# design.net
KiCad netlist of a schematic drawn in Altium Designer
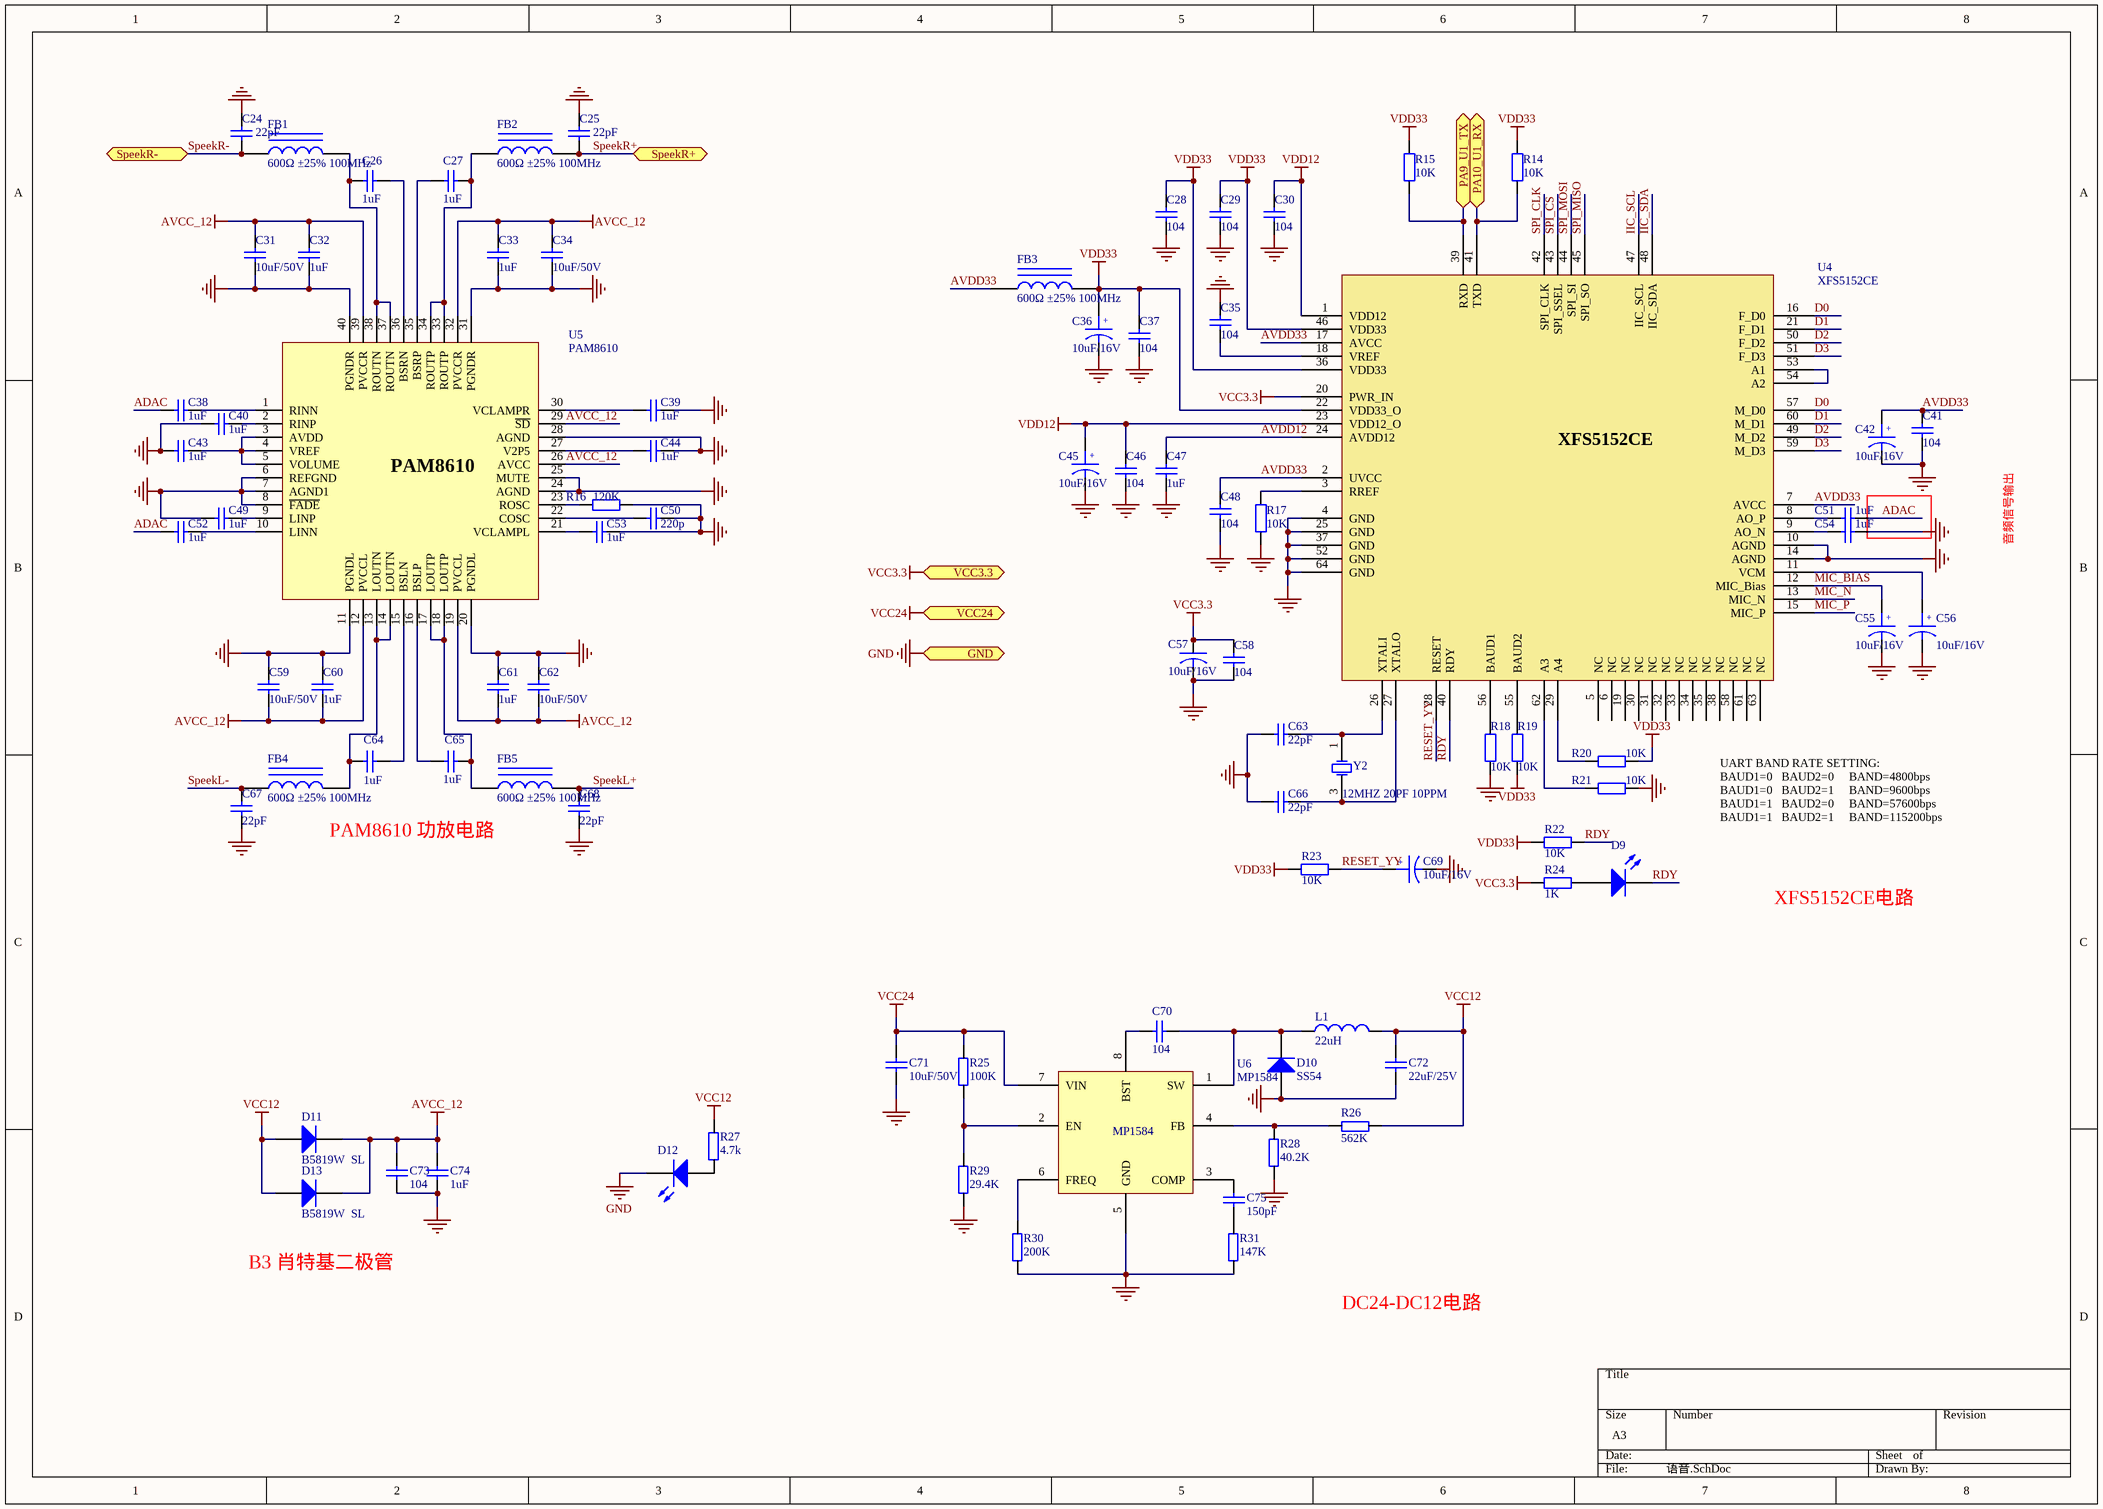
[diagram p0: 语音.SchDoc]

(export (version "E")
  (design (tool "Eeschema 10.0.6"))
  (components
    (comp (ref "C24")
      (value "22pF")
      (footprint "0603_C")
      (description "Capacitor (Semiconductor SIM Model)")
      (fields (field (name "PUBLISHER") "Altium Limited"))
      (libsource (lib "Miscellaneous Devices") (part "Cap Semi"))
    )
    (comp (ref "C25")
      (value "22pF")
      (footprint "0603_C")
      (description "Capacitor (Semiconductor SIM Model)")
      (fields (field (name "PUBLISHER") "Altium Limited"))
      (libsource (lib "Miscellaneous Devices") (part "Cap Semi"))
    )
    (comp (ref "C26")
      (value "1uF")
      (footprint "0603_C")
      (description "Capacitor (Semiconductor SIM Model)")
      (fields (field (name "PUBLISHER") "Altium Limited"))
      (libsource (lib "Miscellaneous Devices") (part "Cap Semi"))
    )
    (comp (ref "C27")
      (value "1uF")
      (footprint "0603_C")
      (description "Capacitor (Semiconductor SIM Model)")
      (fields (field (name "PUBLISHER") "Altium Limited"))
      (libsource (lib "Miscellaneous Devices") (part "Cap Semi"))
    )
    (comp (ref "C28")
      (value "104")
      (footprint "0603_C")
      (description "Capacitor (Semiconductor SIM Model)")
      (fields (field (name "PUBLISHER") "Altium Limited"))
      (libsource (lib "Miscellaneous Devices") (part "Cap Semi"))
    )
    (comp (ref "C29")
      (value "104")
      (footprint "0603_C")
      (description "Capacitor (Semiconductor SIM Model)")
      (fields (field (name "PUBLISHER") "Altium Limited"))
      (libsource (lib "Miscellaneous Devices") (part "Cap Semi"))
    )
    (comp (ref "C30")
      (value "104")
      (footprint "0603_C")
      (description "Capacitor (Semiconductor SIM Model)")
      (fields (field (name "PUBLISHER") "Altium Limited"))
      (libsource (lib "Miscellaneous Devices") (part "Cap Semi"))
    )
    (comp (ref "C31")
      (value "10uF/50V")
      (footprint "1206_C")
      (description "电容")
      (fields (field (name "PUBLISHER") "Altium Limited"))
      (libsource (lib "*") (part "Cap NP"))
    )
    (comp (ref "C32")
      (value "1uF")
      (footprint "0603_C")
      (description "Capacitor (Semiconductor SIM Model)")
      (fields (field (name "PUBLISHER") "Altium Limited"))
      (libsource (lib "Miscellaneous Devices") (part "Cap Semi"))
    )
    (comp (ref "C33")
      (value "1uF")
      (footprint "0603_C")
      (description "Capacitor (Semiconductor SIM Model)")
      (fields (field (name "PUBLISHER") "Altium Limited"))
      (libsource (lib "Miscellaneous Devices") (part "Cap Semi"))
    )
    (comp (ref "C34")
      (value "10uF/50V")
      (footprint "1206_C")
      (description "电容")
      (fields (field (name "PUBLISHER") "Altium Limited"))
      (libsource (lib "*") (part "Cap NP"))
    )
    (comp (ref "C35")
      (value "104")
      (footprint "0603_C")
      (description "Capacitor (Semiconductor SIM Model)")
      (fields (field (name "PUBLISHER") "Altium Limited"))
      (libsource (lib "Miscellaneous Devices") (part "Cap Semi"))
    )
    (comp (ref "C36") (value "10uF/16V") (footprint "3216") (libsource (lib "*") (part "CAP POL")))
    (comp (ref "C37")
      (value "104")
      (footprint "0603_C")
      (description "Capacitor (Semiconductor SIM Model)")
      (fields (field (name "PUBLISHER") "Altium Limited"))
      (libsource (lib "Miscellaneous Devices") (part "Cap Semi"))
    )
    (comp (ref "C38")
      (value "1uF")
      (footprint "0603_C")
      (description "Capacitor (Semiconductor SIM Model)")
      (fields (field (name "PUBLISHER") "Altium Limited"))
      (libsource (lib "Miscellaneous Devices") (part "Cap Semi"))
    )
    (comp (ref "C39")
      (value "1uF")
      (footprint "0603_C")
      (description "Capacitor (Semiconductor SIM Model)")
      (fields (field (name "PUBLISHER") "Altium Limited"))
      (libsource (lib "Miscellaneous Devices") (part "Cap Semi"))
    )
    (comp (ref "C40")
      (value "1uF")
      (footprint "0603_C")
      (description "Capacitor (Semiconductor SIM Model)")
      (fields (field (name "PUBLISHER") "Altium Limited"))
      (libsource (lib "Miscellaneous Devices") (part "Cap Semi"))
    )
    (comp (ref "C41")
      (value "104")
      (footprint "0603_C")
      (description "Capacitor (Semiconductor SIM Model)")
      (fields (field (name "PUBLISHER") "Altium Limited"))
      (libsource (lib "Miscellaneous Devices") (part "Cap Semi"))
    )
    (comp (ref "C42") (value "10uF/16V") (footprint "3216") (libsource (lib "*") (part "CAP POL")))
    (comp (ref "C43")
      (value "1uF")
      (footprint "0603_C")
      (description "Capacitor (Semiconductor SIM Model)")
      (fields (field (name "PUBLISHER") "Altium Limited"))
      (libsource (lib "Miscellaneous Devices") (part "Cap Semi"))
    )
    (comp (ref "C44")
      (value "1uF")
      (footprint "0603_C")
      (description "Capacitor (Semiconductor SIM Model)")
      (fields (field (name "PUBLISHER") "Altium Limited"))
      (libsource (lib "Miscellaneous Devices") (part "Cap Semi"))
    )
    (comp (ref "C45") (value "10uF/16V") (footprint "3216") (libsource (lib "*") (part "CAP POL")))
    (comp (ref "C46")
      (value "104")
      (footprint "0603_C")
      (description "Capacitor (Semiconductor SIM Model)")
      (fields (field (name "PUBLISHER") "Altium Limited"))
      (libsource (lib "Miscellaneous Devices") (part "Cap Semi"))
    )
    (comp (ref "C47")
      (value "1uF")
      (footprint "0603_C")
      (description "Capacitor (Semiconductor SIM Model)")
      (fields (field (name "PUBLISHER") "Altium Limited"))
      (libsource (lib "Miscellaneous Devices") (part "Cap Semi"))
    )
    (comp (ref "C48")
      (value "104")
      (footprint "0603_C")
      (description "Capacitor (Semiconductor SIM Model)")
      (fields (field (name "PUBLISHER") "Altium Limited"))
      (libsource (lib "Miscellaneous Devices") (part "Cap Semi"))
    )
    (comp (ref "C49")
      (value "1uF")
      (footprint "0603_C")
      (description "Capacitor (Semiconductor SIM Model)")
      (fields (field (name "PUBLISHER") "Altium Limited"))
      (libsource (lib "Miscellaneous Devices") (part "Cap Semi"))
    )
    (comp (ref "C50")
      (value "220p")
      (footprint "0603_C")
      (description "Capacitor (Semiconductor SIM Model)")
      (fields (field (name "PUBLISHER") "Altium Limited"))
      (libsource (lib "Miscellaneous Devices") (part "Cap Semi"))
    )
    (comp (ref "C51")
      (value "1uF")
      (footprint "0603_C")
      (description "Capacitor (Semiconductor SIM Model)")
      (fields (field (name "PUBLISHER") "Altium Limited"))
      (libsource (lib "Miscellaneous Devices") (part "Cap Semi"))
    )
    (comp (ref "C52")
      (value "1uF")
      (footprint "0603_C")
      (description "Capacitor (Semiconductor SIM Model)")
      (fields (field (name "PUBLISHER") "Altium Limited"))
      (libsource (lib "Miscellaneous Devices") (part "Cap Semi"))
    )
    (comp (ref "C53")
      (value "1uF")
      (footprint "0603_C")
      (description "Capacitor (Semiconductor SIM Model)")
      (fields (field (name "PUBLISHER") "Altium Limited"))
      (libsource (lib "Miscellaneous Devices") (part "Cap Semi"))
    )
    (comp (ref "C54")
      (value "1uF")
      (footprint "0603_C")
      (description "Capacitor (Semiconductor SIM Model)")
      (fields (field (name "PUBLISHER") "Altium Limited"))
      (libsource (lib "Miscellaneous Devices") (part "Cap Semi"))
    )
    (comp (ref "C55") (value "10uF/16V") (footprint "3216") (libsource (lib "*") (part "CAP POL")))
    (comp (ref "C56") (value "10uF/16V") (footprint "3216") (libsource (lib "*") (part "CAP POL")))
    (comp (ref "C57")
      (value "10uF/16V")
      (footprint "3216")
      (description "Capacitor")
      (libsource (lib "*") (part "CAPACITOR"))
    )
    (comp (ref "C58")
      (value "104")
      (footprint "0603_C")
      (description "Capacitor (Semiconductor SIM Model)")
      (fields (field (name "PUBLISHER") "Altium Limited"))
      (libsource (lib "Miscellaneous Devices") (part "Cap Semi"))
    )
    (comp (ref "C59")
      (value "10uF/50V")
      (footprint "1206_C")
      (description "电容")
      (fields (field (name "PUBLISHER") "Altium Limited"))
      (libsource (lib "*") (part "Cap NP"))
    )
    (comp (ref "C60")
      (value "1uF")
      (footprint "0603_C")
      (description "Capacitor (Semiconductor SIM Model)")
      (fields (field (name "PUBLISHER") "Altium Limited"))
      (libsource (lib "Miscellaneous Devices") (part "Cap Semi"))
    )
    (comp (ref "C61")
      (value "1uF")
      (footprint "0603_C")
      (description "Capacitor (Semiconductor SIM Model)")
      (fields (field (name "PUBLISHER") "Altium Limited"))
      (libsource (lib "Miscellaneous Devices") (part "Cap Semi"))
    )
    (comp (ref "C62")
      (value "10uF/50V")
      (footprint "1206_C")
      (description "电容")
      (fields (field (name "PUBLISHER") "Altium Limited"))
      (libsource (lib "*") (part "Cap NP"))
    )
    (comp (ref "C63")
      (value "22pF")
      (footprint "0603_C")
      (description "电容")
      (fields (field (name "PUBLISHER") "Altium Limited"))
      (libsource (lib "*") (part "Cap NP"))
    )
    (comp (ref "C64")
      (value "1uF")
      (footprint "0603_C")
      (description "Capacitor (Semiconductor SIM Model)")
      (fields (field (name "PUBLISHER") "Altium Limited"))
      (libsource (lib "Miscellaneous Devices") (part "Cap Semi"))
    )
    (comp (ref "C65")
      (value "1uF")
      (footprint "0603_C")
      (description "Capacitor (Semiconductor SIM Model)")
      (fields (field (name "PUBLISHER") "Altium Limited"))
      (libsource (lib "Miscellaneous Devices") (part "Cap Semi"))
    )
    (comp (ref "C66")
      (value "22pF")
      (footprint "0603_C")
      (description "电容")
      (fields (field (name "PUBLISHER") "Altium Limited"))
      (libsource (lib "*") (part "Cap NP"))
    )
    (comp (ref "C67")
      (value "22pF")
      (footprint "0603_C")
      (description "Capacitor (Semiconductor SIM Model)")
      (fields (field (name "PUBLISHER") "Altium Limited"))
      (libsource (lib "Miscellaneous Devices") (part "Cap Semi"))
    )
    (comp (ref "C68")
      (value "22pF")
      (footprint "0603_C")
      (description "Capacitor (Semiconductor SIM Model)")
      (fields (field (name "PUBLISHER") "Altium Limited"))
      (libsource (lib "Miscellaneous Devices") (part "Cap Semi"))
    )
    (comp (ref "C69") (value "10uF/16V") (footprint "3216") (libsource (lib "*") (part "CAP POL")))
    (comp (ref "C70")
      (value "104")
      (footprint "0603_C")
      (description "Capacitor (Semiconductor SIM Model)")
      (fields (field (name "PUBLISHER") "Altium Limited"))
      (libsource (lib "Miscellaneous Devices") (part "Cap Semi"))
    )
    (comp (ref "C71")
      (value "10uF/50V")
      (footprint "1206_C")
      (description "Capacitor (Semiconductor SIM Model)")
      (fields (field (name "PUBLISHER") "Altium Limited"))
      (libsource (lib "Miscellaneous Devices") (part "Cap Semi"))
    )
    (comp (ref "C72")
      (value "22uF/25V")
      (footprint "0805_C")
      (description "Capacitor (Semiconductor SIM Model)")
      (fields (field (name "PUBLISHER") "Altium Limited"))
      (libsource (lib "Miscellaneous Devices") (part "Cap Semi"))
    )
    (comp (ref "C73")
      (value "104")
      (footprint "0603_C")
      (description "Capacitor (Semiconductor SIM Model)")
      (fields (field (name "PUBLISHER") "Altium Limited"))
      (libsource (lib "Miscellaneous Devices") (part "Cap Semi"))
    )
    (comp (ref "C74")
      (value "1uF")
      (footprint "0603_C")
      (description "Capacitor (Semiconductor SIM Model)")
      (fields (field (name "PUBLISHER") "Altium Limited"))
      (libsource (lib "Miscellaneous Devices") (part "Cap Semi"))
    )
    (comp (ref "C75")
      (value "150pF")
      (footprint "0603_C")
      (description "Capacitor (Semiconductor SIM Model)")
      (fields (field (name "PUBLISHER") "Altium Limited"))
      (libsource (lib "Miscellaneous Devices") (part "Cap Semi"))
    )
    (comp (ref "D9")
      (value "红灯 0805")
      (footprint "LC-0805_LED_S1")
      (description "Typical INFRARED GaAs LED")
      (fields (field (name "PUBLISHER") "Altium Limited"))
      (libsource (lib "继电器板_1") (part "LED0"))
    )
    (comp (ref "D10")
      (value "SS54")
      (footprint "SMA(DO-214AC)_S1")
      (description "二极管")
      (libsource (lib "Miscellaneous Devices LC") (part "SMA(DO-214AC) SS54"))
    )
    (comp (ref "D11")
      (value "B5819W  SL")
      (footprint "SOD-123")
      (description "肖特基二极管")
      (libsource (lib "Miscellaneous Devices LC") (part "SOD-123 B5819W  SL"))
    )
    (comp (ref "D12")
      (value "蓝灯 0805")
      (footprint "LC-0805_LED_S1")
      (description "Typical INFRARED GaAs LED")
      (fields (field (name "PUBLISHER") "Altium Limited"))
      (libsource (lib "继电器板_1") (part "LED0"))
    )
    (comp (ref "D13")
      (value "B5819W  SL")
      (footprint "SOD-123")
      (description "肖特基二极管")
      (libsource (lib "Miscellaneous Devices LC") (part "SOD-123 B5819W  SL"))
    )
    (comp (ref "FB1")
      (value "600Ω ±25% 100MHz")
      (footprint "0805_L")
      (description "贴片磁珠")
      (libsource (lib "Miscellaneous Devices LC") (part "0805 600Ω 25% 100MHz"))
    )
    (comp (ref "FB2")
      (value "600Ω ±25% 100MHz")
      (footprint "0805_L")
      (description "贴片磁珠")
      (libsource (lib "Miscellaneous Devices LC") (part "0805 600Ω 25% 100MHz"))
    )
    (comp (ref "FB3")
      (value "600Ω ±25% 100MHz")
      (footprint "0805_L")
      (description "贴片磁珠")
      (libsource (lib "Miscellaneous Devices LC") (part "0805 600Ω 25% 100MHz"))
    )
    (comp (ref "FB4")
      (value "600Ω ±25% 100MHz")
      (footprint "0805_L")
      (description "贴片磁珠")
      (libsource (lib "Miscellaneous Devices LC") (part "0805 600Ω 25% 100MHz"))
    )
    (comp (ref "FB5")
      (value "600Ω ±25% 100MHz")
      (footprint "0805_L")
      (description "贴片磁珠")
      (libsource (lib "Miscellaneous Devices LC") (part "0805 600Ω 25% 100MHz"))
    )
    (comp (ref "L1")
      (value "22uH")
      (footprint "L-7*7*4mm-S")
      (description "Inductor")
      (fields (field (name "PUBLISHER") "Altium Limited"))
      (libsource (lib "Miscellaneous Devices") (part "Inductor"))
    )
    (comp (ref "R14")
      (value "10K")
      (footprint "0603_R")
      (description "Resistor")
      (fields (field (name "PUBLISHER") "Altium Limited"))
      (libsource (lib "") (part "Res2_3"))
    )
    (comp (ref "R15")
      (value "10K")
      (footprint "0603_R")
      (description "Resistor")
      (fields (field (name "PUBLISHER") "Altium Limited"))
      (libsource (lib "") (part "Res2_2"))
    )
    (comp (ref "R16")
      (value "120K")
      (footprint "0603_R")
      (description "Resistor")
      (fields (field (name "PUBLISHER") "Altium Limited"))
      (libsource (lib "") (part "Res2_1"))
    )
    (comp (ref "R17")
      (value "10K")
      (footprint "0603_R")
      (description "Resistor")
      (fields (field (name "PUBLISHER") "Altium Limited"))
      (libsource (lib "") (part "Res2_3"))
    )
    (comp (ref "R18")
      (value "10K")
      (footprint "0603_R")
      (description "Resistor")
      (fields (field (name "PUBLISHER") "Altium Limited"))
      (libsource (lib "") (part "Res2_2"))
    )
    (comp (ref "R19")
      (value "10K")
      (footprint "0603_R")
      (description "Resistor")
      (fields (field (name "PUBLISHER") "Altium Limited"))
      (libsource (lib "") (part "Res2_2"))
    )
    (comp (ref "R20")
      (value "10K")
      (footprint "0603_R")
      (description "Resistor")
      (fields (field (name "PUBLISHER") "Altium Limited"))
      (libsource (lib "*") (part "Res2"))
    )
    (comp (ref "R21")
      (value "10K")
      (footprint "0603_R")
      (description "Resistor")
      (fields (field (name "PUBLISHER") "Altium Limited"))
      (libsource (lib "") (part "Res2_1"))
    )
    (comp (ref "R22")
      (value "10K")
      (footprint "0603_R")
      (description "Resistor")
      (fields (field (name "PUBLISHER") "Altium Limited"))
      (libsource (lib "*") (part "Res2"))
    )
    (comp (ref "R23")
      (value "10K")
      (footprint "0603_R")
      (description "Resistor")
      (fields (field (name "PUBLISHER") "Altium Limited"))
      (libsource (lib "*") (part "Res2"))
    )
    (comp (ref "R24")
      (value "1K")
      (footprint "0603_R")
      (description "Resistor")
      (fields (field (name "PUBLISHER") "Altium Limited"))
      (libsource (lib "*") (part "Res2"))
    )
    (comp (ref "R25")
      (value "100K")
      (footprint "0603_R")
      (libsource (lib "Explorer STM32F407封装库") (part "R_2"))
    )
    (comp (ref "R26")
      (value "562K")
      (footprint "0603_R")
      (libsource (lib "Explorer STM32F407封装库") (part "R_2"))
    )
    (comp (ref "R27")
      (value "4.7k")
      (footprint "0603_R")
      (libsource (lib "Explorer STM32F407封装库") (part "R_2"))
    )
    (comp (ref "R28")
      (value "40.2K")
      (footprint "0603_R")
      (libsource (lib "Explorer STM32F407封装库") (part "R_2"))
    )
    (comp (ref "R29")
      (value "29.4K")
      (footprint "0603_R")
      (libsource (lib "Explorer STM32F407封装库") (part "R_2"))
    )
    (comp (ref "R30")
      (value "200K")
      (footprint "0603_R")
      (libsource (lib "Explorer STM32F407封装库") (part "R_2"))
    )
    (comp (ref "R31")
      (value "147K")
      (footprint "0603_R")
      (libsource (lib "Explorer STM32F407封装库") (part "R_2"))
    )
    (comp (ref "U4")
      (value "XFS5152CE")
      (footprint "LQFP-64_10x10x05P")
      (libsource (lib "*") (part "XFS5152-2"))
    )
    (comp (ref "U5")
      (value "PAM8610")
      (footprint "QFN50P600X600X80-40N")
      (libsource (lib "my third") (part "PAM8610功放芯片"))
    )
    (comp (ref "U6")
      (value "MP1584")
      (footprint "LC-SOIC-8_EP_150MIL")
      (libsource (lib "磁导航") (part "MP1584EN"))
    )
    (comp (ref "Y2")
      (value "12MHZ 20PF 10PPM")
      (footprint "SMD-3225_4P")
      (description "贴片晶振")
      (libsource (lib "Miscellaneous Devices LC") (part "SMD-3225_4P  12MHZ 20PF 10PPM"))
    )
  )
  (nets
    (net (code "1") (name "/ADAC") (class "Default")
      (node (ref "C38") (pin "1") (pinfunction "1_1") (pintype "passive"))
      (node (ref "C51") (pin "1") (pinfunction "1_1") (pintype "passive"))
      (node (ref "C52") (pin "1") (pinfunction "1_1") (pintype "passive"))
    )
    (net (code "2") (name "/AVDD12") (class "Default")
      (node (ref "C47") (pin "2") (pinfunction "2_2") (pintype "passive"))
      (node (ref "U4") (pin "24") (pinfunction "AVDD12_24") (pintype "passive"))
    )
    (net (code "3") (name "/AVDD33") (class "Default")
      (node (ref "C41") (pin "1") (pinfunction "1_1") (pintype "passive"))
      (node (ref "C42") (pin "1") (pinfunction "1_1") (pintype "passive"))
      (node (ref "C48") (pin "1") (pinfunction "1_1") (pintype "passive"))
      (node (ref "FB3") (pin "1") (pinfunction "1_1") (pintype "passive"))
      (node (ref "U4") (pin "17") (pinfunction "AVCC_17") (pintype "passive"))
      (node (ref "U4") (pin "2") (pinfunction "UVCC_2") (pintype "passive"))
      (node (ref "U4") (pin "7") (pinfunction "AVCC_7") (pintype "passive"))
    )
    (net (code "4") (name "/D0") (class "Default")
      (node (ref "U4") (pin "16") (pinfunction "F_D0_16") (pintype "passive"))
      (node (ref "U4") (pin "57") (pinfunction "M_D0_57") (pintype "passive"))
    )
    (net (code "5") (name "/D1") (class "Default")
      (node (ref "U4") (pin "21") (pinfunction "F_D1_21") (pintype "passive"))
      (node (ref "U4") (pin "60") (pinfunction "M_D1_60") (pintype "passive"))
    )
    (net (code "6") (name "/D2") (class "Default")
      (node (ref "U4") (pin "49") (pinfunction "M_D2_49") (pintype "passive"))
      (node (ref "U4") (pin "50") (pinfunction "F_D2_50") (pintype "passive"))
    )
    (net (code "7") (name "/D3") (class "Default")
      (node (ref "U4") (pin "51") (pinfunction "F_D3_51") (pintype "passive"))
      (node (ref "U4") (pin "59") (pinfunction "M_D3_59") (pintype "passive"))
    )
    (net (code "8") (name "/IIC_SCL") (class "Default")
      (node (ref "U4") (pin "47") (pinfunction "IIC_SCL_47") (pintype "passive"))
    )
    (net (code "9") (name "/IIC_SDA") (class "Default")
      (node (ref "U4") (pin "48") (pinfunction "IIC_SDA_48") (pintype "passive"))
    )
    (net (code "10") (name "/MIC_BIAS") (class "Default")
      (node (ref "C55") (pin "1") (pinfunction "1_1") (pintype "passive"))
      (node (ref "U4") (pin "12") (pinfunction "MIC_Bias_12") (pintype "passive"))
    )
    (net (code "11") (name "/MIC_N") (class "Default")
      (node (ref "U4") (pin "13") (pinfunction "MIC_N_13") (pintype "passive"))
    )
    (net (code "12") (name "/MIC_P") (class "Default")
      (node (ref "U4") (pin "15") (pinfunction "MIC_P_15") (pintype "passive"))
    )
    (net (code "13") (name "/PA9_U1_TX") (class "Default")
      (node (ref "R15") (pin "2") (pinfunction "2_2") (pintype "passive"))
      (node (ref "U4") (pin "39") (pinfunction "RXD_39") (pintype "passive"))
    )
    (net (code "14") (name "/PA10_U1_RX") (class "Default")
      (node (ref "R14") (pin "1") (pinfunction "1_1") (pintype "passive"))
      (node (ref "U4") (pin "41") (pinfunction "TXD_41") (pintype "passive"))
    )
    (net (code "15") (name "/RDY") (class "Default")
      (node (ref "D9") (pin "K") (pinfunction "K_K") (pintype "passive"))
      (node (ref "R22") (pin "2") (pinfunction "2_2") (pintype "passive"))
      (node (ref "U4") (pin "40") (pinfunction "RDY_40") (pintype "passive"))
    )
    (net (code "16") (name "/RESET_YY") (class "Default")
      (node (ref "C69") (pin "1") (pinfunction "1_1") (pintype "passive"))
      (node (ref "R23") (pin "2") (pinfunction "2_2") (pintype "passive"))
      (node (ref "U4") (pin "28") (pinfunction "RESET_28") (pintype "passive"))
    )
    (net (code "17") (name "/SPI_CLK") (class "Default")
      (node (ref "U4") (pin "42") (pinfunction "SPI_CLK_42") (pintype "passive"))
    )
    (net (code "18") (name "/SPI_CS") (class "Default")
      (node (ref "U4") (pin "43") (pinfunction "SPI_SSEL_43") (pintype "passive"))
    )
    (net (code "19") (name "/SPI_MISO") (class "Default")
      (node (ref "U4") (pin "45") (pinfunction "SPI_SO_45") (pintype "passive"))
    )
    (net (code "20") (name "/SPI_MOSI") (class "Default")
      (node (ref "U4") (pin "44") (pinfunction "SPI_SI_44") (pintype "passive"))
    )
    (net (code "21") (name "/SpeekL+") (class "Default")
      (node (ref "C68") (pin "2") (pinfunction "2_2") (pintype "passive"))
      (node (ref "FB5") (pin "2") (pinfunction "2_2") (pintype "passive"))
    )
    (net (code "22") (name "/SpeekL-") (class "Default")
      (node (ref "C67") (pin "2") (pinfunction "2_2") (pintype "passive"))
      (node (ref "FB4") (pin "1") (pinfunction "1_1") (pintype "passive"))
    )
    (net (code "23") (name "/SpeekR+") (class "Default")
      (node (ref "C25") (pin "2") (pinfunction "2_2") (pintype "passive"))
      (node (ref "FB2") (pin "2") (pinfunction "2_2") (pintype "passive"))
    )
    (net (code "24") (name "/SpeekR-") (class "Default")
      (node (ref "C24") (pin "2") (pinfunction "2_2") (pintype "passive"))
      (node (ref "FB1") (pin "1") (pinfunction "1_1") (pintype "passive"))
    )
    (net (code "25") (name "AVCC_12") (class "Default")
      (node (ref "C31") (pin "1") (pinfunction "1_1") (pintype "passive"))
      (node (ref "C32") (pin "1") (pinfunction "1_1") (pintype "passive"))
      (node (ref "C33") (pin "1") (pinfunction "1_1") (pintype "passive"))
      (node (ref "C34") (pin "1") (pinfunction "1_1") (pintype "passive"))
      (node (ref "C59") (pin "1") (pinfunction "1_1") (pintype "passive"))
      (node (ref "C60") (pin "1") (pinfunction "1_1") (pintype "passive"))
      (node (ref "C61") (pin "1") (pinfunction "1_1") (pintype "passive"))
      (node (ref "C62") (pin "1") (pinfunction "1_1") (pintype "passive"))
      (node (ref "C73") (pin "1") (pinfunction "1_1") (pintype "passive"))
      (node (ref "C74") (pin "1") (pinfunction "1_1") (pintype "passive"))
      (node (ref "D11") (pin "2") (pinfunction "K_2") (pintype "passive"))
      (node (ref "D13") (pin "2") (pinfunction "K_2") (pintype "passive"))
      (node (ref "U5") (pin "12") (pinfunction "PVCCL_12") (pintype "passive"))
      (node (ref "U5") (pin "19") (pinfunction "PVCCL_19") (pintype "passive"))
      (node (ref "U5") (pin "26") (pinfunction "AVCC_26") (pintype "passive"))
      (node (ref "U5") (pin "29") (pinfunction "~{SD}_29") (pintype "passive"))
      (node (ref "U5") (pin "32") (pinfunction "PVCCR_32") (pintype "passive"))
      (node (ref "U5") (pin "39") (pinfunction "PVCCR_39") (pintype "passive"))
    )
    (net (code "26") (name "GND") (class "Default")
      (node (ref "C24") (pin "1") (pinfunction "1_1") (pintype "passive"))
      (node (ref "C25") (pin "1") (pinfunction "1_1") (pintype "passive"))
      (node (ref "C28") (pin "2") (pinfunction "2_2") (pintype "passive"))
      (node (ref "C29") (pin "2") (pinfunction "2_2") (pintype "passive"))
      (node (ref "C30") (pin "2") (pinfunction "2_2") (pintype "passive"))
      (node (ref "C31") (pin "2") (pinfunction "2_2") (pintype "passive"))
      (node (ref "C32") (pin "2") (pinfunction "2_2") (pintype "passive"))
      (node (ref "C33") (pin "2") (pinfunction "2_2") (pintype "passive"))
      (node (ref "C34") (pin "2") (pinfunction "2_2") (pintype "passive"))
      (node (ref "C35") (pin "1") (pinfunction "1_1") (pintype "passive"))
      (node (ref "C36") (pin "2") (pinfunction "2_2") (pintype "passive"))
      (node (ref "C37") (pin "2") (pinfunction "2_2") (pintype "passive"))
      (node (ref "C39") (pin "2") (pinfunction "2_2") (pintype "passive"))
      (node (ref "C40") (pin "1") (pinfunction "1_1") (pintype "passive"))
      (node (ref "C41") (pin "2") (pinfunction "2_2") (pintype "passive"))
      (node (ref "C42") (pin "2") (pinfunction "2_2") (pintype "passive"))
      (node (ref "C43") (pin "1") (pinfunction "1_1") (pintype "passive"))
      (node (ref "C44") (pin "2") (pinfunction "2_2") (pintype "passive"))
      (node (ref "C45") (pin "2") (pinfunction "2_2") (pintype "passive"))
      (node (ref "C46") (pin "2") (pinfunction "2_2") (pintype "passive"))
      (node (ref "C47") (pin "1") (pinfunction "1_1") (pintype "passive"))
      (node (ref "C48") (pin "2") (pinfunction "2_2") (pintype "passive"))
      (node (ref "C49") (pin "1") (pinfunction "1_1") (pintype "passive"))
      (node (ref "C50") (pin "2") (pinfunction "2_2") (pintype "passive"))
      (node (ref "C53") (pin "2") (pinfunction "2_2") (pintype "passive"))
      (node (ref "C54") (pin "1") (pinfunction "1_1") (pintype "passive"))
      (node (ref "C55") (pin "2") (pinfunction "2_2") (pintype "passive"))
      (node (ref "C56") (pin "2") (pinfunction "2_2") (pintype "passive"))
      (node (ref "C57") (pin "2") (pinfunction "2_2") (pintype "passive"))
      (node (ref "C58") (pin "2") (pinfunction "2_2") (pintype "passive"))
      (node (ref "C59") (pin "2") (pinfunction "2_2") (pintype "passive"))
      (node (ref "C60") (pin "2") (pinfunction "2_2") (pintype "passive"))
      (node (ref "C61") (pin "2") (pinfunction "2_2") (pintype "passive"))
      (node (ref "C62") (pin "2") (pinfunction "2_2") (pintype "passive"))
      (node (ref "C63") (pin "1") (pinfunction "1_1") (pintype "passive"))
      (node (ref "C66") (pin "1") (pinfunction "1_1") (pintype "passive"))
      (node (ref "C67") (pin "1") (pinfunction "1_1") (pintype "passive"))
      (node (ref "C68") (pin "1") (pinfunction "1_1") (pintype "passive"))
      (node (ref "C69") (pin "2") (pinfunction "2_2") (pintype "passive"))
      (node (ref "C71") (pin "2") (pinfunction "2_2") (pintype "passive"))
      (node (ref "C72") (pin "1") (pinfunction "1_1") (pintype "passive"))
      (node (ref "C73") (pin "2") (pinfunction "2_2") (pintype "passive"))
      (node (ref "C74") (pin "2") (pinfunction "2_2") (pintype "passive"))
      (node (ref "D10") (pin "1") (pinfunction "A_1") (pintype "passive"))
      (node (ref "D12") (pin "K") (pinfunction "K_K") (pintype "passive"))
      (node (ref "R16") (pin "1") (pinfunction "1_1") (pintype "passive"))
      (node (ref "R17") (pin "1") (pinfunction "1_1") (pintype "passive"))
      (node (ref "R18") (pin "2") (pinfunction "2_2") (pintype "passive"))
      (node (ref "R21") (pin "1") (pinfunction "1_1") (pintype "passive"))
      (node (ref "R28") (pin "2") (pintype "passive"))
      (node (ref "R29") (pin "2") (pintype "passive"))
      (node (ref "R30") (pin "2") (pintype "passive"))
      (node (ref "R31") (pin "2") (pintype "passive"))
      (node (ref "U4") (pin "10") (pinfunction "AGND_10") (pintype "passive"))
      (node (ref "U4") (pin "14") (pinfunction "AGND_14") (pintype "passive"))
      (node (ref "U4") (pin "25") (pinfunction "GND_25") (pintype "passive"))
      (node (ref "U4") (pin "37") (pinfunction "GND_37") (pintype "passive"))
      (node (ref "U4") (pin "4") (pinfunction "GND_4") (pintype "passive"))
      (node (ref "U4") (pin "52") (pinfunction "GND_52") (pintype "passive"))
      (node (ref "U4") (pin "64") (pinfunction "GND_64") (pintype "passive"))
      (node (ref "U5") (pin "11") (pinfunction "PGNDL_11") (pintype "passive"))
      (node (ref "U5") (pin "20") (pinfunction "PGNDL_20") (pintype "passive"))
      (node (ref "U5") (pin "24") (pinfunction "AGND_24") (pintype "passive"))
      (node (ref "U5") (pin "25") (pinfunction "MUTE_25") (pintype "passive"))
      (node (ref "U5") (pin "28") (pinfunction "AGND_28") (pintype "passive"))
      (node (ref "U5") (pin "31") (pinfunction "PGNDR_31") (pintype "passive"))
      (node (ref "U5") (pin "40") (pinfunction "PGNDR_40") (pintype "passive"))
      (node (ref "U5") (pin "6") (pinfunction "REFGND_6") (pintype "passive"))
      (node (ref "U5") (pin "7") (pinfunction "AGND1_7") (pintype "passive"))
      (node (ref "U5") (pin "8") (pinfunction "~{FADE}_8") (pintype "passive"))
      (node (ref "U6") (pin "5") (pinfunction "GND_5") (pintype "passive"))
    )
    (net (code "27") (name "Net-(C26-Pad1)") (class "Default")
      (node (ref "C26") (pin "1") (pinfunction "1_1") (pintype "passive"))
      (node (ref "FB1") (pin "2") (pinfunction "2_2") (pintype "passive"))
      (node (ref "U5") (pin "37") (pinfunction "ROUTN_37") (pintype "passive"))
      (node (ref "U5") (pin "38") (pinfunction "ROUTN_38") (pintype "passive"))
    )
    (net (code "28") (name "Net-(C27-Pad2)") (class "Default")
      (node (ref "C27") (pin "2") (pinfunction "2_2") (pintype "passive"))
      (node (ref "FB2") (pin "1") (pinfunction "1_1") (pintype "passive"))
      (node (ref "U5") (pin "33") (pinfunction "ROUTP_33") (pintype "passive"))
      (node (ref "U5") (pin "34") (pinfunction "ROUTP_34") (pintype "passive"))
    )
    (net (code "29") (name "Net-(C64-Pad2)") (class "Default")
      (node (ref "C64") (pin "2") (pinfunction "2_2") (pintype "passive"))
      (node (ref "FB4") (pin "2") (pinfunction "2_2") (pintype "passive"))
      (node (ref "U5") (pin "13") (pinfunction "LOUTN_13") (pintype "passive"))
      (node (ref "U5") (pin "14") (pinfunction "LOUTN_14") (pintype "passive"))
    )
    (net (code "30") (name "Net-(C65-Pad2)") (class "Default")
      (node (ref "C65") (pin "2") (pinfunction "2_2") (pintype "passive"))
      (node (ref "FB5") (pin "1") (pinfunction "1_1") (pintype "passive"))
      (node (ref "U5") (pin "17") (pinfunction "LOUTP_17") (pintype "passive"))
      (node (ref "U5") (pin "18") (pinfunction "LOUTP_18") (pintype "passive"))
    )
    (net (code "31") (name "Net-(C75-Pad1)") (class "Default")
      (node (ref "C75") (pin "1") (pinfunction "1_1") (pintype "passive"))
      (node (ref "R31") (pin "1") (pintype "passive"))
    )
    (net (code "32") (name "Net-(D9-PadA)") (class "Default")
      (node (ref "D9") (pin "A") (pinfunction "A_A") (pintype "passive"))
      (node (ref "R24") (pin "2") (pinfunction "2_2") (pintype "passive"))
    )
    (net (code "33") (name "Net-(D10-K)") (class "Default")
      (node (ref "C70") (pin "1") (pinfunction "1_1") (pintype "passive"))
      (node (ref "D10") (pin "2") (pinfunction "K_2") (pintype "passive"))
      (node (ref "L1") (pin "1") (pinfunction "1_1") (pintype "passive"))
      (node (ref "U6") (pin "1") (pinfunction "SW_1") (pintype "passive"))
    )
    (net (code "34") (name "Net-(D12-PadA)") (class "Default")
      (node (ref "D12") (pin "A") (pinfunction "A_A") (pintype "passive"))
      (node (ref "R27") (pin "2") (pintype "passive"))
    )
    (net (code "35") (name "Net-(U4-A1)") (class "Default")
      (node (ref "U4") (pin "53") (pinfunction "A1_53") (pintype "passive"))
      (node (ref "U4") (pin "54") (pinfunction "A2_54") (pintype "passive"))
    )
    (net (code "36") (name "Net-(U4-A3)") (class "Default")
      (node (ref "R21") (pin "2") (pinfunction "2_2") (pintype "passive"))
      (node (ref "U4") (pin "62") (pinfunction "A3_62") (pintype "passive"))
    )
    (net (code "37") (name "Net-(U4-A4)") (class "Default")
      (node (ref "R20") (pin "1") (pinfunction "1_1") (pintype "passive"))
      (node (ref "U4") (pin "29") (pinfunction "A4_29") (pintype "passive"))
    )
    (net (code "38") (name "Net-(U4-AO_N)") (class "Default")
      (node (ref "C54") (pin "2") (pinfunction "2_2") (pintype "passive"))
      (node (ref "U4") (pin "9") (pinfunction "AO_N_9") (pintype "passive"))
    )
    (net (code "39") (name "Net-(U4-AO_P)") (class "Default")
      (node (ref "C51") (pin "2") (pinfunction "2_2") (pintype "passive"))
      (node (ref "U4") (pin "8") (pinfunction "AO_P_8") (pintype "passive"))
    )
    (net (code "40") (name "Net-(U4-BAUD1)") (class "Default")
      (node (ref "R18") (pin "1") (pinfunction "1_1") (pintype "passive"))
      (node (ref "U4") (pin "56") (pinfunction "BAUD1_56") (pintype "passive"))
    )
    (net (code "41") (name "Net-(U4-BAUD2)") (class "Default")
      (node (ref "R19") (pin "1") (pinfunction "1_1") (pintype "passive"))
      (node (ref "U4") (pin "55") (pinfunction "BAUD2_55") (pintype "passive"))
    )
    (net (code "42") (name "Net-(U4-RREF)") (class "Default")
      (node (ref "R17") (pin "2") (pinfunction "2_2") (pintype "passive"))
      (node (ref "U4") (pin "3") (pinfunction "RREF_3") (pintype "passive"))
    )
    (net (code "43") (name "Net-(U4-VCM)") (class "Default")
      (node (ref "C56") (pin "1") (pinfunction "1_1") (pintype "passive"))
      (node (ref "U4") (pin "11") (pinfunction "VCM_11") (pintype "passive"))
    )
    (net (code "44") (name "Net-(U4-VREF)") (class "Default")
      (node (ref "C35") (pin "2") (pinfunction "2_2") (pintype "passive"))
      (node (ref "U4") (pin "18") (pinfunction "VREF_18") (pintype "passive"))
    )
    (net (code "45") (name "Net-(U4-XTALI)") (class "Default")
      (node (ref "C63") (pin "2") (pinfunction "2_2") (pintype "passive"))
      (node (ref "U4") (pin "26") (pinfunction "XTALI_26") (pintype "passive"))
      (node (ref "Y2") (pin "1") (pinfunction "OSC1_1") (pintype "passive"))
    )
    (net (code "46") (name "Net-(U4-XTALO)") (class "Default")
      (node (ref "C66") (pin "2") (pinfunction "2_2") (pintype "passive"))
      (node (ref "U4") (pin "27") (pinfunction "XTALO_27") (pintype "passive"))
      (node (ref "Y2") (pin "3") (pinfunction "OSC2_3") (pintype "passive"))
    )
    (net (code "47") (name "Net-(U5-AVDD)") (class "Default")
      (node (ref "C43") (pin "2") (pinfunction "2_2") (pintype "passive"))
      (node (ref "U5") (pin "3") (pinfunction "AVDD_3") (pintype "passive"))
      (node (ref "U5") (pin "4") (pinfunction "VREF_4") (pintype "passive"))
      (node (ref "U5") (pin "5") (pinfunction "VOLUME_5") (pintype "passive"))
    )
    (net (code "48") (name "Net-(U5-BSLN)") (class "Default")
      (node (ref "C64") (pin "1") (pinfunction "1_1") (pintype "passive"))
      (node (ref "U5") (pin "15") (pinfunction "BSLN_15") (pintype "passive"))
    )
    (net (code "49") (name "Net-(U5-BSLP)") (class "Default")
      (node (ref "C65") (pin "1") (pinfunction "1_1") (pintype "passive"))
      (node (ref "U5") (pin "16") (pinfunction "BSLP_16") (pintype "passive"))
    )
    (net (code "50") (name "Net-(U5-BSRN)") (class "Default")
      (node (ref "C26") (pin "2") (pinfunction "2_2") (pintype "passive"))
      (node (ref "U5") (pin "36") (pinfunction "BSRN_36") (pintype "passive"))
    )
    (net (code "51") (name "Net-(U5-BSRP)") (class "Default")
      (node (ref "C27") (pin "1") (pinfunction "1_1") (pintype "passive"))
      (node (ref "U5") (pin "35") (pinfunction "BSRP_35") (pintype "passive"))
    )
    (net (code "52") (name "Net-(U5-COSC)") (class "Default")
      (node (ref "C50") (pin "1") (pinfunction "1_1") (pintype "passive"))
      (node (ref "U5") (pin "22") (pinfunction "COSC_22") (pintype "passive"))
    )
    (net (code "53") (name "Net-(U5-LINN)") (class "Default")
      (node (ref "C52") (pin "2") (pinfunction "2_2") (pintype "passive"))
      (node (ref "U5") (pin "10") (pinfunction "LINN_10") (pintype "passive"))
    )
    (net (code "54") (name "Net-(U5-LINP)") (class "Default")
      (node (ref "C49") (pin "2") (pinfunction "2_2") (pintype "passive"))
      (node (ref "U5") (pin "9") (pinfunction "LINP_9") (pintype "passive"))
    )
    (net (code "55") (name "Net-(U5-RINN)") (class "Default")
      (node (ref "C38") (pin "2") (pinfunction "2_2") (pintype "passive"))
      (node (ref "U5") (pin "1") (pinfunction "RINN_1") (pintype "passive"))
    )
    (net (code "56") (name "Net-(U5-RINP)") (class "Default")
      (node (ref "C40") (pin "2") (pinfunction "2_2") (pintype "passive"))
      (node (ref "U5") (pin "2") (pinfunction "RINP_2") (pintype "passive"))
    )
    (net (code "57") (name "Net-(U5-ROSC)") (class "Default")
      (node (ref "R16") (pin "2") (pinfunction "2_2") (pintype "passive"))
      (node (ref "U5") (pin "23") (pinfunction "ROSC_23") (pintype "passive"))
    )
    (net (code "58") (name "Net-(U5-V2P5)") (class "Default")
      (node (ref "C44") (pin "1") (pinfunction "1_1") (pintype "passive"))
      (node (ref "U5") (pin "27") (pinfunction "V2P5_27") (pintype "passive"))
    )
    (net (code "59") (name "Net-(U5-VCLAMPL)") (class "Default")
      (node (ref "C53") (pin "1") (pinfunction "1_1") (pintype "passive"))
      (node (ref "U5") (pin "21") (pinfunction "VCLAMPL_21") (pintype "passive"))
    )
    (net (code "60") (name "Net-(U5-VCLAMPR)") (class "Default")
      (node (ref "C39") (pin "1") (pinfunction "1_1") (pintype "passive"))
      (node (ref "U5") (pin "30") (pinfunction "VCLAMPR_30") (pintype "passive"))
    )
    (net (code "61") (name "Net-(U6-BST)") (class "Default")
      (node (ref "C70") (pin "2") (pinfunction "2_2") (pintype "passive"))
      (node (ref "U6") (pin "8") (pinfunction "BST_8") (pintype "passive"))
    )
    (net (code "62") (name "Net-(U6-COMP)") (class "Default")
      (node (ref "C75") (pin "2") (pinfunction "2_2") (pintype "passive"))
      (node (ref "U6") (pin "3") (pinfunction "COMP_3") (pintype "passive"))
    )
    (net (code "63") (name "Net-(U6-EN)") (class "Default")
      (node (ref "R25") (pin "2") (pintype "passive"))
      (node (ref "R29") (pin "1") (pintype "passive"))
      (node (ref "U6") (pin "2") (pinfunction "EN_2") (pintype "passive"))
    )
    (net (code "64") (name "Net-(U6-FB)") (class "Default")
      (node (ref "R26") (pin "1") (pintype "passive"))
      (node (ref "R28") (pin "1") (pintype "passive"))
      (node (ref "U6") (pin "4") (pinfunction "FB_4") (pintype "passive"))
    )
    (net (code "65") (name "Net-(U6-FREQ)") (class "Default")
      (node (ref "R30") (pin "1") (pintype "passive"))
      (node (ref "U6") (pin "6") (pinfunction "FREQ_6") (pintype "passive"))
    )
    (net (code "66") (name "VCC3.3") (class "Default")
      (node (ref "C57") (pin "1") (pinfunction "1_1") (pintype "passive"))
      (node (ref "C58") (pin "1") (pinfunction "1_1") (pintype "passive"))
      (node (ref "R24") (pin "1") (pinfunction "1_1") (pintype "passive"))
      (node (ref "U4") (pin "20") (pinfunction "PWR_IN_20") (pintype "passive"))
    )
    (net (code "67") (name "VCC12") (class "Default")
      (node (ref "C72") (pin "2") (pinfunction "2_2") (pintype "passive"))
      (node (ref "D11") (pin "1") (pinfunction "A_1") (pintype "passive"))
      (node (ref "D13") (pin "1") (pinfunction "A_1") (pintype "passive"))
      (node (ref "L1") (pin "2") (pinfunction "2_2") (pintype "passive"))
      (node (ref "R26") (pin "2") (pintype "passive"))
      (node (ref "R27") (pin "1") (pintype "passive"))
    )
    (net (code "68") (name "VCC24") (class "Default")
      (node (ref "C71") (pin "1") (pinfunction "1_1") (pintype "passive"))
      (node (ref "R25") (pin "1") (pintype "passive"))
      (node (ref "U6") (pin "7") (pinfunction "VIN_7") (pintype "passive"))
    )
    (net (code "69") (name "VDD12") (class "Default")
      (node (ref "C30") (pin "1") (pinfunction "1_1") (pintype "passive"))
      (node (ref "C45") (pin "1") (pinfunction "1_1") (pintype "passive"))
      (node (ref "C46") (pin "1") (pinfunction "1_1") (pintype "passive"))
      (node (ref "U4") (pin "1") (pinfunction "VDD12_1") (pintype "passive"))
      (node (ref "U4") (pin "23") (pinfunction "VDD12_O_23") (pintype "passive"))
    )
    (net (code "70") (name "VDD33") (class "Default")
      (node (ref "C28") (pin "1") (pinfunction "1_1") (pintype "passive"))
      (node (ref "C29") (pin "1") (pinfunction "1_1") (pintype "passive"))
      (node (ref "C36") (pin "1") (pinfunction "1_1") (pintype "passive"))
      (node (ref "C37") (pin "1") (pinfunction "1_1") (pintype "passive"))
      (node (ref "FB3") (pin "2") (pinfunction "2_2") (pintype "passive"))
      (node (ref "R14") (pin "2") (pinfunction "2_2") (pintype "passive"))
      (node (ref "R15") (pin "1") (pinfunction "1_1") (pintype "passive"))
      (node (ref "R19") (pin "2") (pinfunction "2_2") (pintype "passive"))
      (node (ref "R20") (pin "2") (pinfunction "2_2") (pintype "passive"))
      (node (ref "R22") (pin "1") (pinfunction "1_1") (pintype "passive"))
      (node (ref "R23") (pin "1") (pinfunction "1_1") (pintype "passive"))
      (node (ref "U4") (pin "22") (pinfunction "VDD33_O_22") (pintype "passive"))
      (node (ref "U4") (pin "36") (pinfunction "VDD33_36") (pintype "passive"))
      (node (ref "U4") (pin "46") (pinfunction "VDD33_46") (pintype "passive"))
    )
    (net (code "71") (name "unconnected-(U4-NC-Pad5)") (class "Default")
      (node (ref "U4") (pin "5") (pinfunction "NC_5") (pintype "passive"))
    )
    (net (code "72") (name "unconnected-(U4-NC-Pad6)") (class "Default")
      (node (ref "U4") (pin "6") (pinfunction "NC_6") (pintype "passive"))
    )
    (net (code "73") (name "unconnected-(U4-NC-Pad19)") (class "Default")
      (node (ref "U4") (pin "19") (pinfunction "NC_19") (pintype "passive"))
    )
    (net (code "74") (name "unconnected-(U4-NC-Pad30)") (class "Default")
      (node (ref "U4") (pin "30") (pinfunction "NC_30") (pintype "passive"))
    )
    (net (code "75") (name "unconnected-(U4-NC-Pad31)") (class "Default")
      (node (ref "U4") (pin "31") (pinfunction "NC_31") (pintype "passive"))
    )
    (net (code "76") (name "unconnected-(U4-NC-Pad32)") (class "Default")
      (node (ref "U4") (pin "32") (pinfunction "NC_32") (pintype "passive"))
    )
    (net (code "77") (name "unconnected-(U4-NC-Pad33)") (class "Default")
      (node (ref "U4") (pin "33") (pinfunction "NC_33") (pintype "passive"))
    )
    (net (code "78") (name "unconnected-(U4-NC-Pad34)") (class "Default")
      (node (ref "U4") (pin "34") (pinfunction "NC_34") (pintype "passive"))
    )
    (net (code "79") (name "unconnected-(U4-NC-Pad35)") (class "Default")
      (node (ref "U4") (pin "35") (pinfunction "NC_35") (pintype "passive"))
    )
    (net (code "80") (name "unconnected-(U4-NC-Pad38)") (class "Default")
      (node (ref "U4") (pin "38") (pinfunction "NC_38") (pintype "passive"))
    )
    (net (code "81") (name "unconnected-(U4-NC-Pad58)") (class "Default")
      (node (ref "U4") (pin "58") (pinfunction "NC_58") (pintype "passive"))
    )
    (net (code "82") (name "unconnected-(U4-NC-Pad61)") (class "Default")
      (node (ref "U4") (pin "61") (pinfunction "NC_61") (pintype "passive"))
    )
    (net (code "83") (name "unconnected-(U4-NC-Pad63)") (class "Default")
      (node (ref "U4") (pin "63") (pinfunction "NC_63") (pintype "passive"))
    )
  )
)
